# SCH_GroeiAcademie-Stimulus-Hardware-Shie.net
KiCad netlist of a schematic drawn in EasyEDA
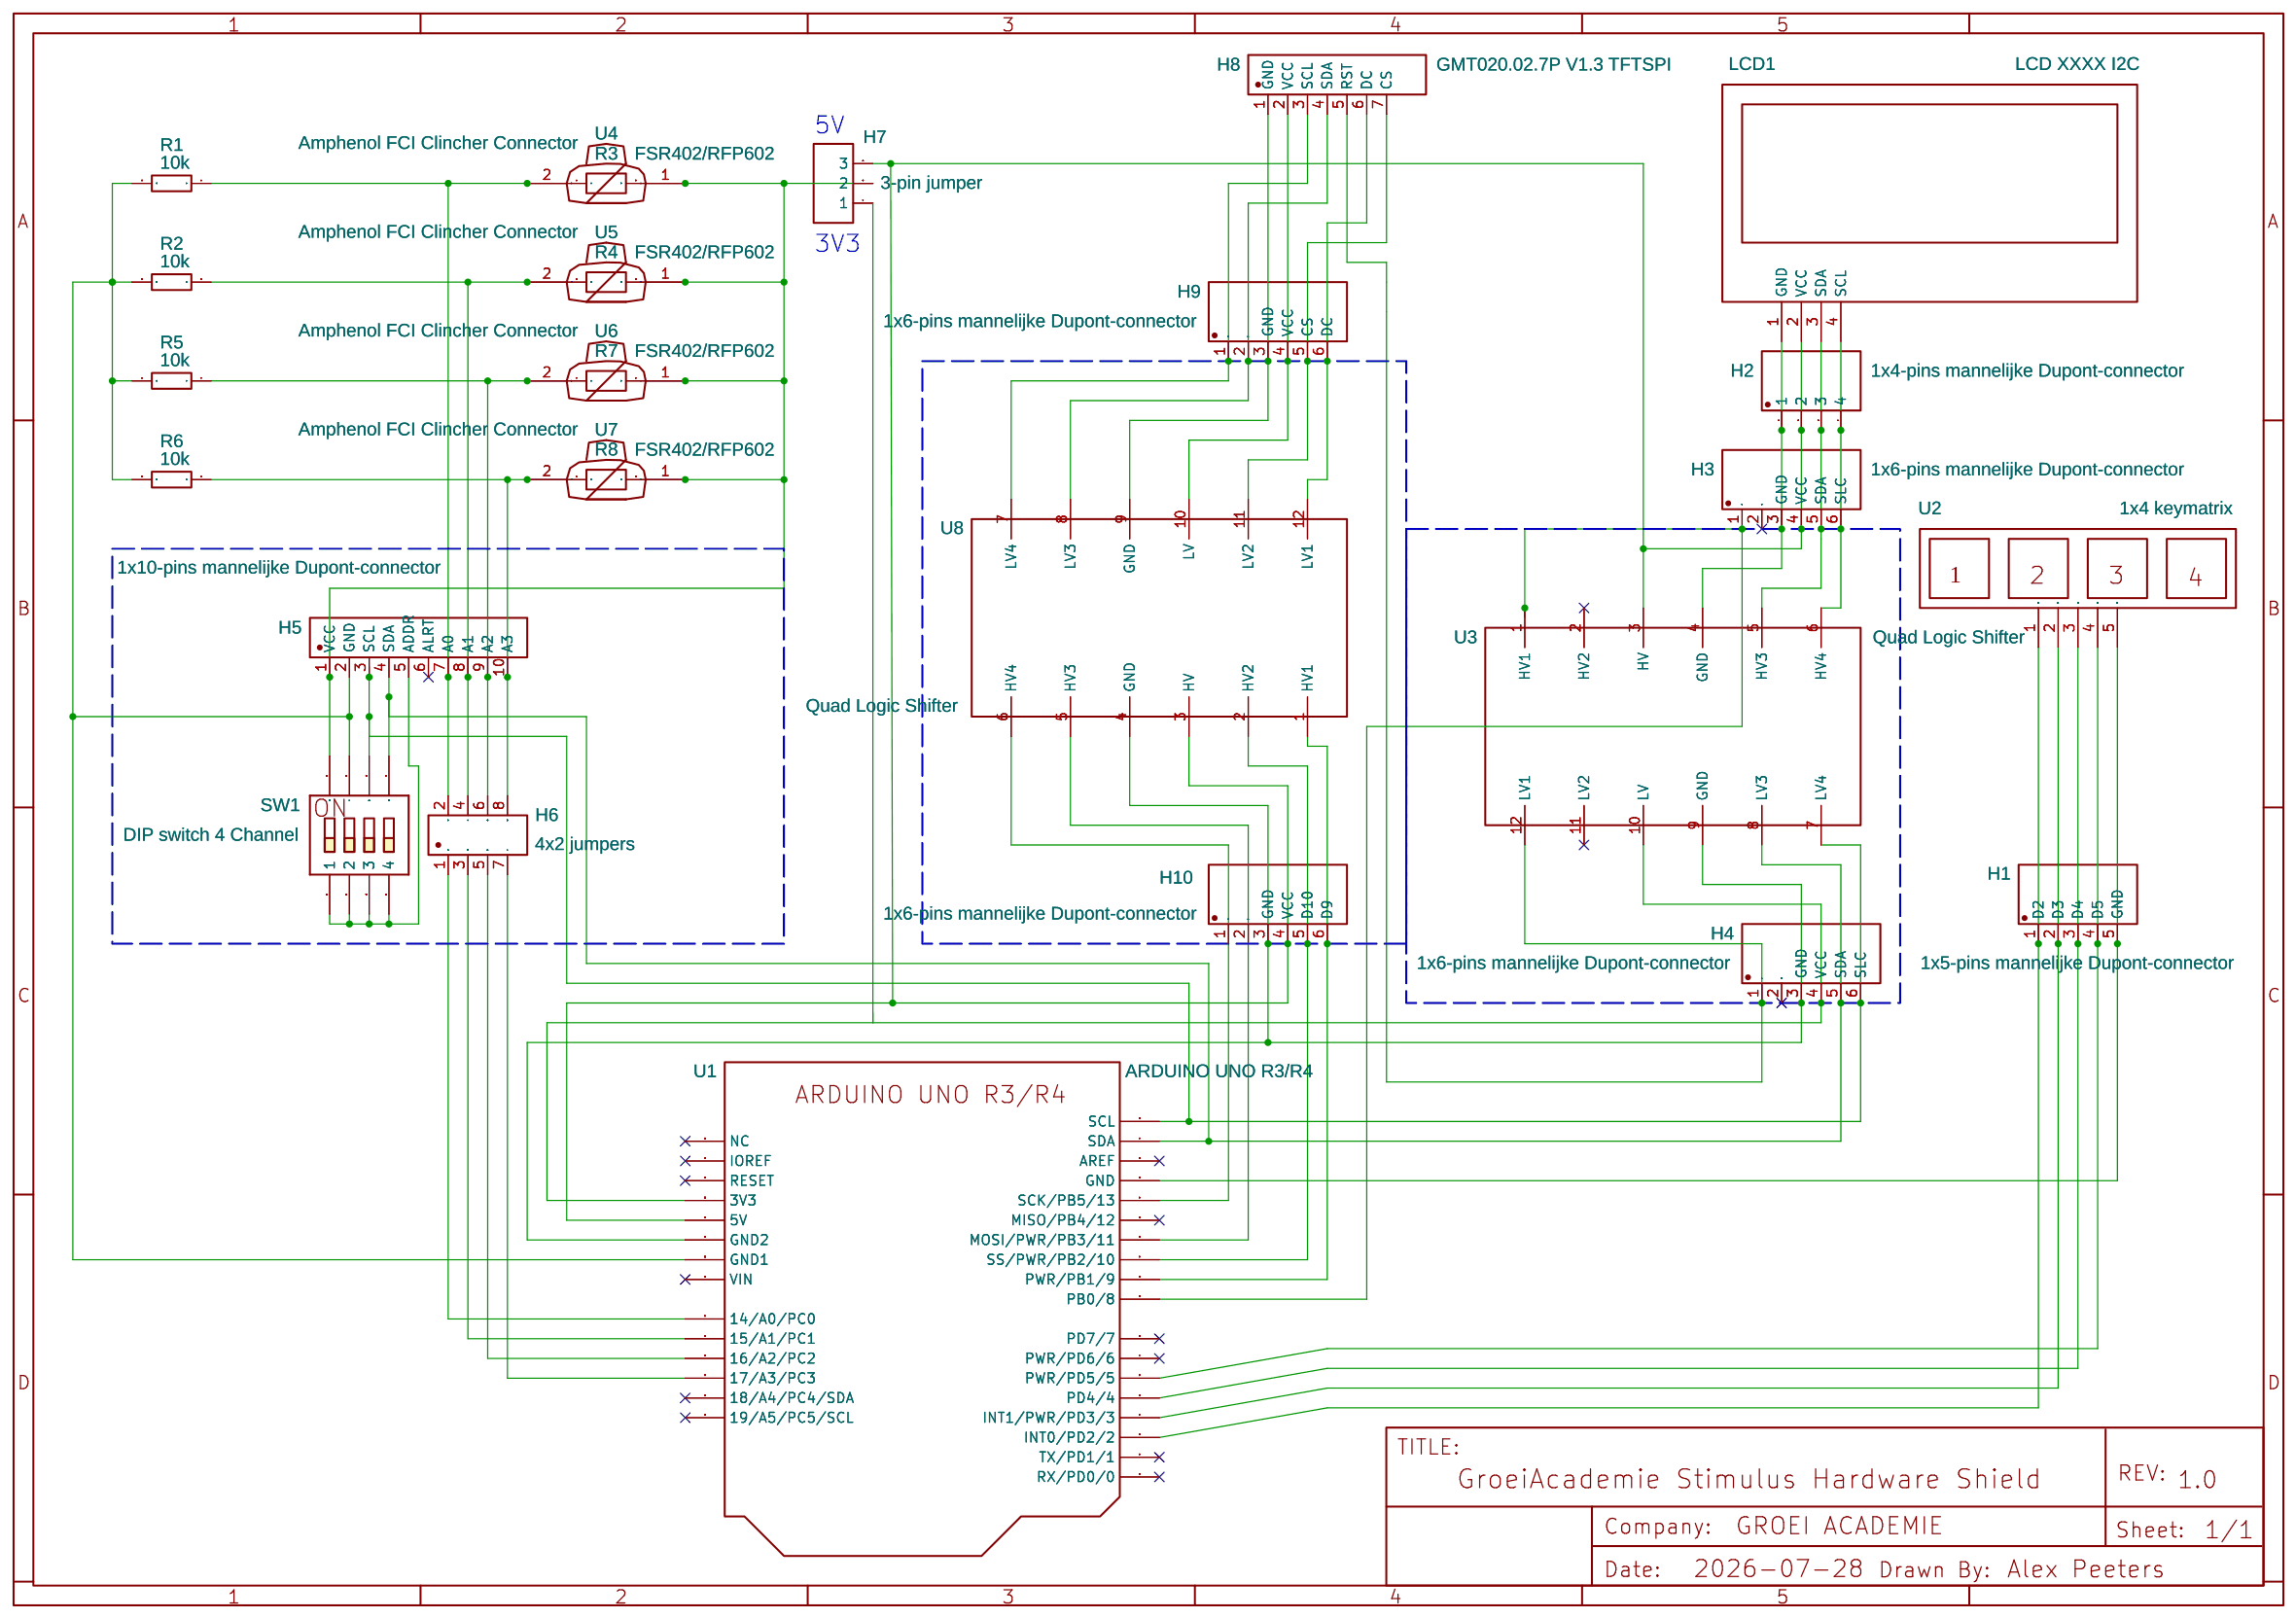
[diagram p0: schematic sheet]

(export (version "E")
  (design (tool "Eeschema 10.0.6"))
  (components
    (comp (ref "H1")
      (value "1x5-pins mannelijke Dupont-connector")
      (fields (field (name "Manufacturer Part") "B-2100S05P-A110") (field (name "Manufacturer") "Ckmtw(灿科盟)"))
      (libsource (lib "") (part "210S-1*5P L=11.6MMGold-plated black"))
    )
    (comp (ref "H2")
      (value "1x4-pins mannelijke Dupont-connector")
      (fields (field (name "Manufacturer Part") "B-2100S04P-A110") (field (name "Manufacturer") "Ckmtw(灿科盟)"))
      (libsource (lib "") (part "Header-Male-2.54_1x4"))
    )
    (comp (ref "H3")
      (value "1x6-pins mannelijke Dupont-connector")
      (fields (field (name "Manufacturer Part") "B-2100S06P-A110") (field (name "Manufacturer") "Ckmtw(灿科盟)"))
      (libsource (lib "") (part "210S-1*6P L=11.6MMGold-plated black"))
    )
    (comp (ref "H4")
      (value "1x6-pins mannelijke Dupont-connector")
      (fields (field (name "Manufacturer Part") "B-2100S06P-A110") (field (name "Manufacturer") "Ckmtw(灿科盟)"))
      (libsource (lib "") (part "210S-1*6P L=11.6MMGold-plated black"))
    )
    (comp (ref "H5")
      (value "1x10-pins mannelijke Dupont-connector")
      (fields (field (name "Manufacturer Part") "2.54-1*10") (field (name "Manufacturer") "ZHOURI(洲日)"))
      (libsource (lib "") (part "2.54-1*10"))
    )
    (comp (ref "H6")
      (value "4x2 jumpers")
      (fields (field (name "Manufacturer Part") "2.54-2*4P立贴针") (field (name "Manufacturer") "BOOMELE(博穆精密)"))
      (libsource (lib "") (part "2.54-2*4P立贴针"))
    )
    (comp (ref "H7") (value "3-pin jumper") (libsource (lib "") (part "HDR-F-2.54_1x3")))
    (comp (ref "H8")
      (value "GMT020.02.7P V1.3 TFTSPI")
      (fields (field (name "Manufacturer Part") "HDR-M-L12-3+4-1x8P-2.54"))
      (libsource (lib "") (part "PZ254R-11-08P"))
    )
    (comp (ref "H9")
      (value "1x6-pins mannelijke Dupont-connector")
      (fields (field (name "Manufacturer Part") "B-2100S06P-A110") (field (name "Manufacturer") "Ckmtw(灿科盟)"))
      (libsource (lib "") (part "210S-1*6P L=11.6MMGold-plated black_1"))
    )
    (comp (ref "H10")
      (value "1x6-pins mannelijke Dupont-connector")
      (fields (field (name "Manufacturer Part") "B-2100S06P-A110") (field (name "Manufacturer") "Ckmtw(灿科盟)"))
      (libsource (lib "") (part "210S-1*6P L=11.6MMGold-plated black_2"))
    )
    (comp (ref "LCD1") (value "LCD XXXX I2C") (libsource (lib "") (part "I2CLCD16X2_N")))
    (comp (ref "R1")
      (value "10k")
      (fields (field (name "Manufacturer") "Made in China"))
      (libsource (lib "") (part "330Ω (331) ±5%"))
    )
    (comp (ref "R2")
      (value "10k")
      (fields (field (name "Manufacturer") "Made in China"))
      (libsource (lib "") (part "330Ω (331) ±5%"))
    )
    (comp (ref "R3") (value "FSR402/RFP602") (libsource (lib "") (part "FSR402-OPCION1")))
    (comp (ref "R4") (value "FSR402/RFP602") (libsource (lib "") (part "FSR402-OPCION1")))
    (comp (ref "R5")
      (value "10k")
      (fields (field (name "Manufacturer") "Made in China"))
      (libsource (lib "") (part "330Ω (331) ±5%"))
    )
    (comp (ref "R6")
      (value "10k")
      (fields (field (name "Manufacturer") "Made in China"))
      (libsource (lib "") (part "330Ω (331) ±5%"))
    )
    (comp (ref "R7") (value "FSR402/RFP602") (libsource (lib "") (part "FSR402-OPCION1")))
    (comp (ref "R8") (value "FSR402/RFP602") (libsource (lib "") (part "FSR402-OPCION1")))
    (comp (ref "SW1")
      (value "DIP switch 4 Channel")
      (fields
        (field (name "Manufacturer Part") "DIP switch,Dip Switch,DSWB04LHGET")
        (field (name "Manufacturer") "KE")
      )
      (libsource (lib "") (part "DIP switch 4 Channel"))
    )
    (comp (ref "U1") (value "ARDUINO UNO R3/R4") (libsource (lib "") (part "ARDUINO UNO r3")))
    (comp (ref "U2") (value "1x4 keymatrix") (libsource (lib "") (part "Клавиатура 4*4")))
    (comp (ref "U3") (value "Quad Logic Shifter") (libsource (lib "") (part "Quad Logic Shifter_1")))
    (comp (ref "U4")
      (value "Amphenol FCI Clincher Connector")
      (fields (field (name "Manufacturer Part") "AT04-2P-BM02") (field (name "Manufacturer") "Amphenol"))
      (libsource (lib "") (part "AT04-2P"))
    )
    (comp (ref "U5")
      (value "Amphenol FCI Clincher Connector")
      (fields (field (name "Manufacturer Part") "AT04-2P-BM02") (field (name "Manufacturer") "Amphenol"))
      (libsource (lib "") (part "AT04-2P"))
    )
    (comp (ref "U6")
      (value "Amphenol FCI Clincher Connector")
      (fields (field (name "Manufacturer Part") "AT04-2P-BM02") (field (name "Manufacturer") "Amphenol"))
      (libsource (lib "") (part "AT04-2P"))
    )
    (comp (ref "U7")
      (value "Amphenol FCI Clincher Connector")
      (fields (field (name "Manufacturer Part") "AT04-2P-BM02") (field (name "Manufacturer") "Amphenol"))
      (libsource (lib "") (part "AT04-2P"))
    )
    (comp (ref "U8") (value "Quad Logic Shifter") (libsource (lib "") (part "Quad Logic Shifter")))
  )
  (nets
    (net (code "1") (name "Net-(H1-D2)") (class "Default")
      (node (ref "H1") (pin "1") (pinfunction "D2_1") (pintype "unspecified"))
      (node (ref "U1") (pin "3") (pinfunction "INT0/PD2/2_3") (pintype "unspecified"))
      (node (ref "U2") (pin "1") (pinfunction "C1_1") (pintype "unspecified"))
    )
    (net (code "2") (name "Net-(H1-D3)") (class "Default")
      (node (ref "H1") (pin "2") (pinfunction "D3_2") (pintype "unspecified"))
      (node (ref "U1") (pin "4") (pinfunction "INT1/PWR/PD3/3_4") (pintype "unspecified"))
      (node (ref "U2") (pin "2") (pinfunction "C2_2") (pintype "unspecified"))
    )
    (net (code "3") (name "Net-(H1-D4)") (class "Default")
      (node (ref "H1") (pin "3") (pinfunction "D4_3") (pintype "unspecified"))
      (node (ref "U1") (pin "5") (pinfunction "PD4/4_5") (pintype "unspecified"))
      (node (ref "U2") (pin "3") (pinfunction "C3_3") (pintype "unspecified"))
    )
    (net (code "4") (name "Net-(H1-D5)") (class "Default")
      (node (ref "H1") (pin "4") (pinfunction "D5_4") (pintype "unspecified"))
      (node (ref "U1") (pin "6") (pinfunction "PWR/PD5/5_6") (pintype "unspecified"))
      (node (ref "U2") (pin "4") (pinfunction "R1_4") (pintype "unspecified"))
    )
    (net (code "5") (name "Net-(H1-GND)") (class "Default")
      (node (ref "H1") (pin "5") (pinfunction "GND_5") (pintype "unspecified"))
      (node (ref "U1") (pin "15") (pinfunction "GND_15") (pintype "passive"))
      (node (ref "U2") (pin "5") (pinfunction "R2_5") (pintype "unspecified"))
    )
    (net (code "6") (name "Net-(H3-GND)") (class "Default")
      (node (ref "H2") (pin "1") (pinfunction "1_1") (pintype "unspecified"))
      (node (ref "H3") (pin "3") (pinfunction "GND_3") (pintype "unspecified"))
      (node (ref "LCD1") (pin "1") (pinfunction "GND_1") (pintype "unspecified"))
      (node (ref "U3") (pin "4") (pinfunction "GND_4") (pintype "unspecified"))
    )
    (net (code "7") (name "Net-(H3-SDA)") (class "Default")
      (node (ref "H2") (pin "3") (pinfunction "3_3") (pintype "unspecified"))
      (node (ref "H3") (pin "5") (pinfunction "SDA_5") (pintype "unspecified"))
      (node (ref "LCD1") (pin "3") (pinfunction "SDA_3") (pintype "unspecified"))
      (node (ref "U3") (pin "5") (pinfunction "HV3_5") (pintype "unspecified"))
    )
    (net (code "8") (name "Net-(H3-SLC)") (class "Default")
      (node (ref "H2") (pin "4") (pinfunction "4_4") (pintype "unspecified"))
      (node (ref "H3") (pin "6") (pinfunction "SLC_6") (pintype "unspecified"))
      (node (ref "LCD1") (pin "4") (pinfunction "SCL_4") (pintype "unspecified"))
      (node (ref "U3") (pin "6") (pinfunction "HV4_6") (pintype "unspecified"))
    )
    (net (code "9") (name "Net-(H4-SDA)") (class "Default")
      (node (ref "H4") (pin "5") (pinfunction "SDA_5") (pintype "unspecified"))
      (node (ref "H5") (pin "4") (pinfunction "SDA_4") (pintype "unspecified"))
      (node (ref "SW1") (pin "4I") (pinfunction "5_4I") (pintype "input"))
      (node (ref "U1") (pin "17") (pinfunction "SDA_17") (pintype "unspecified"))
      (node (ref "U3") (pin "8") (pinfunction "LV3_8") (pintype "unspecified"))
    )
    (net (code "10") (name "Net-(H4-SLC)") (class "Default")
      (node (ref "H4") (pin "6") (pinfunction "SLC_6") (pintype "unspecified"))
      (node (ref "H5") (pin "3") (pinfunction "SCL_3") (pintype "unspecified"))
      (node (ref "SW1") (pin "3I") (pinfunction "6_3I") (pintype "input"))
      (node (ref "U1") (pin "18") (pinfunction "SCL_18") (pintype "unspecified"))
      (node (ref "U3") (pin "7") (pinfunction "LV4_7") (pintype "unspecified"))
    )
    (net (code "11") (name "Net-(H4-VCC)") (class "Default")
      (node (ref "H4") (pin "4") (pinfunction "VCC_4") (pintype "unspecified"))
      (node (ref "U1") (pin "29") (pinfunction "3V3_29") (pintype "passive"))
      (node (ref "U3") (pin "10") (pinfunction "LV_10") (pintype "unspecified"))
    )
    (net (code "12") (name "Net-(H5-A0)") (class "Default")
      (node (ref "H5") (pin "7") (pinfunction "A0_7") (pintype "unspecified"))
      (node (ref "H6") (pin "2") (pinfunction "2_2") (pintype "unspecified"))
      (node (ref "R1") (pin "1") (pinfunction "1_1") (pintype "unspecified"))
      (node (ref "R3") (pin "1") (pinfunction "1_1") (pintype "unspecified"))
      (node (ref "U4") (pin "2") (pinfunction "2_2") (pintype "unspecified"))
    )
    (net (code "13") (name "Net-(H5-A1)") (class "Default")
      (node (ref "H5") (pin "8") (pinfunction "A1_8") (pintype "unspecified"))
      (node (ref "H6") (pin "4") (pinfunction "4_4") (pintype "unspecified"))
      (node (ref "R2") (pin "1") (pinfunction "1_1") (pintype "unspecified"))
      (node (ref "R4") (pin "1") (pinfunction "1_1") (pintype "unspecified"))
      (node (ref "U5") (pin "2") (pinfunction "2_2") (pintype "unspecified"))
    )
    (net (code "14") (name "Net-(H5-A2)") (class "Default")
      (node (ref "H5") (pin "9") (pinfunction "A2_9") (pintype "unspecified"))
      (node (ref "H6") (pin "6") (pinfunction "6_6") (pintype "unspecified"))
      (node (ref "R5") (pin "1") (pinfunction "1_1") (pintype "unspecified"))
      (node (ref "R7") (pin "1") (pinfunction "1_1") (pintype "unspecified"))
      (node (ref "U6") (pin "2") (pinfunction "2_2") (pintype "unspecified"))
    )
    (net (code "15") (name "Net-(H5-A3)") (class "Default")
      (node (ref "H5") (pin "10") (pinfunction "A3_10") (pintype "unspecified"))
      (node (ref "H6") (pin "8") (pinfunction "8_8") (pintype "unspecified"))
      (node (ref "R6") (pin "1") (pinfunction "1_1") (pintype "unspecified"))
      (node (ref "R8") (pin "1") (pinfunction "1_1") (pintype "unspecified"))
      (node (ref "U7") (pin "2") (pinfunction "2_2") (pintype "unspecified"))
    )
    (net (code "16") (name "Net-(H5-ADDR)") (class "Default")
      (node (ref "H5") (pin "5") (pinfunction "ADDR_5") (pintype "unspecified"))
      (node (ref "SW1") (pin "1O") (pinfunction "1_1O") (pintype "input"))
      (node (ref "SW1") (pin "2O") (pinfunction "2_2O") (pintype "input"))
      (node (ref "SW1") (pin "3O") (pinfunction "3_3O") (pintype "input"))
      (node (ref "SW1") (pin "4O") (pinfunction "4_4O") (pintype "input"))
    )
    (net (code "17") (name "Net-(H5-GND)") (class "Default")
      (node (ref "H5") (pin "2") (pinfunction "GND_2") (pintype "unspecified"))
      (node (ref "R1") (pin "2") (pinfunction "2_2") (pintype "unspecified"))
      (node (ref "R2") (pin "2") (pinfunction "2_2") (pintype "unspecified"))
      (node (ref "R5") (pin "2") (pinfunction "2_2") (pintype "unspecified"))
      (node (ref "R6") (pin "2") (pinfunction "2_2") (pintype "unspecified"))
      (node (ref "SW1") (pin "2I") (pinfunction "7_2I") (pintype "input"))
      (node (ref "U1") (pin "26") (pinfunction "GND1_26") (pintype "passive"))
    )
    (net (code "18") (name "Net-(H5-VCC)") (class "Default")
      (node (ref "H5") (pin "1") (pinfunction "VCC_1") (pintype "unspecified"))
      (node (ref "H7") (pin "2") (pinfunction "2_2") (pintype "input"))
      (node (ref "R3") (pin "2") (pinfunction "2_2") (pintype "unspecified"))
      (node (ref "R4") (pin "2") (pinfunction "2_2") (pintype "unspecified"))
      (node (ref "R7") (pin "2") (pinfunction "2_2") (pintype "unspecified"))
      (node (ref "R8") (pin "2") (pinfunction "2_2") (pintype "unspecified"))
      (node (ref "SW1") (pin "1I") (pinfunction "8_1I") (pintype "input"))
      (node (ref "U4") (pin "1") (pinfunction "1_1") (pintype "unspecified"))
      (node (ref "U5") (pin "1") (pinfunction "1_1") (pintype "unspecified"))
      (node (ref "U6") (pin "1") (pinfunction "1_1") (pintype "unspecified"))
      (node (ref "U7") (pin "1") (pinfunction "1_1") (pintype "unspecified"))
    )
    (net (code "19") (name "Net-(H8-CS)") (class "Default")
      (node (ref "H8") (pin "7") (pinfunction "CS_7") (pintype "unspecified"))
      (node (ref "H9") (pin "5") (pinfunction "CS_5") (pintype "unspecified"))
      (node (ref "U8") (pin "11") (pinfunction "LV2_11") (pintype "unspecified"))
    )
    (net (code "20") (name "Net-(H8-DC)") (class "Default")
      (node (ref "H8") (pin "6") (pinfunction "DC_6") (pintype "unspecified"))
      (node (ref "H9") (pin "6") (pinfunction "DC_6") (pintype "unspecified"))
      (node (ref "U8") (pin "12") (pinfunction "LV1_12") (pintype "unspecified"))
    )
    (net (code "21") (name "Net-(H8-GND)") (class "Default")
      (node (ref "H8") (pin "1") (pinfunction "GND_1") (pintype "unspecified"))
      (node (ref "H9") (pin "3") (pinfunction "GND_3") (pintype "unspecified"))
      (node (ref "U8") (pin "9") (pinfunction "GND_9") (pintype "unspecified"))
    )
    (net (code "22") (name "Net-(H8-RST)") (class "Default")
      (node (ref "H4") (pin "1") (pinfunction "1_1") (pintype "unspecified"))
      (node (ref "H8") (pin "5") (pinfunction "RST_5") (pintype "unspecified"))
      (node (ref "U3") (pin "12") (pinfunction "LV1_12") (pintype "unspecified"))
    )
    (net (code "23") (name "Net-(H8-SCL)") (class "Default")
      (node (ref "H8") (pin "3") (pinfunction "SCL_3") (pintype "unspecified"))
      (node (ref "H9") (pin "1") (pinfunction "1_1") (pintype "unspecified"))
      (node (ref "U8") (pin "7") (pinfunction "LV4_7") (pintype "unspecified"))
    )
    (net (code "24") (name "Net-(H8-SDA)") (class "Default")
      (node (ref "H8") (pin "4") (pinfunction "SDA_4") (pintype "unspecified"))
      (node (ref "H9") (pin "2") (pinfunction "2_2") (pintype "unspecified"))
      (node (ref "U8") (pin "8") (pinfunction "LV3_8") (pintype "unspecified"))
    )
    (net (code "25") (name "Net-(H8-VCC)") (class "Default")
      (node (ref "H8") (pin "2") (pinfunction "VCC_2") (pintype "unspecified"))
      (node (ref "H9") (pin "4") (pinfunction "VCC_4") (pintype "unspecified"))
      (node (ref "U8") (pin "10") (pinfunction "LV_10") (pintype "unspecified"))
    )
    (net (code "26") (name "Net-(H10-D9)") (class "Default")
      (node (ref "H10") (pin "6") (pinfunction "D9_6") (pintype "unspecified"))
      (node (ref "U1") (pin "10") (pinfunction "PWR/PB1/9_10") (pintype "unspecified"))
      (node (ref "U8") (pin "1") (pinfunction "HV1_1") (pintype "unspecified"))
    )
    (net (code "27") (name "Net-(H10-D10)") (class "Default")
      (node (ref "H10") (pin "5") (pinfunction "D10_5") (pintype "unspecified"))
      (node (ref "U1") (pin "11") (pinfunction "SS/PWR/PB2/10_11") (pintype "unspecified"))
      (node (ref "U8") (pin "2") (pinfunction "HV2_2") (pintype "unspecified"))
    )
    (net (code "28") (name "Net-(H10-GND)") (class "Default")
      (node (ref "H10") (pin "3") (pinfunction "GND_3") (pintype "unspecified"))
      (node (ref "H4") (pin "3") (pinfunction "GND_3") (pintype "unspecified"))
      (node (ref "U1") (pin "27") (pinfunction "GND2_27") (pintype "passive"))
      (node (ref "U3") (pin "9") (pinfunction "GND_9") (pintype "unspecified"))
      (node (ref "U8") (pin "4") (pinfunction "GND_4") (pintype "unspecified"))
    )
    (net (code "29") (name "Net-(H10-VCC)") (class "Default")
      (node (ref "H10") (pin "4") (pinfunction "VCC_4") (pintype "unspecified"))
      (node (ref "H2") (pin "2") (pinfunction "2_2") (pintype "unspecified"))
      (node (ref "H3") (pin "4") (pinfunction "VCC_4") (pintype "unspecified"))
      (node (ref "H7") (pin "3") (pinfunction "3_3") (pintype "input"))
      (node (ref "LCD1") (pin "2") (pinfunction "VCC_2") (pintype "unspecified"))
      (node (ref "U1") (pin "28") (pinfunction "5V_28") (pintype "passive"))
      (node (ref "U3") (pin "3") (pinfunction "HV_3") (pintype "unspecified"))
      (node (ref "U8") (pin "3") (pinfunction "HV_3") (pintype "unspecified"))
    )
    (net (code "30") (name "Net-(U1-14{slash}A0{slash}PC0)") (class "Default")
      (node (ref "H6") (pin "1") (pinfunction "1_1") (pintype "unspecified"))
      (node (ref "U1") (pin "24") (pinfunction "14/A0/PC0_24") (pintype "unspecified"))
    )
    (net (code "31") (name "Net-(U1-15{slash}A1{slash}PC1)") (class "Default")
      (node (ref "H6") (pin "3") (pinfunction "3_3") (pintype "unspecified"))
      (node (ref "U1") (pin "23") (pinfunction "15/A1/PC1_23") (pintype "unspecified"))
    )
    (net (code "32") (name "Net-(U1-16{slash}A2{slash}PC2)") (class "Default")
      (node (ref "H6") (pin "5") (pinfunction "5_5") (pintype "unspecified"))
      (node (ref "U1") (pin "22") (pinfunction "16/A2/PC2_22") (pintype "unspecified"))
    )
    (net (code "33") (name "Net-(U1-17{slash}A3{slash}PC3)") (class "Default")
      (node (ref "H6") (pin "7") (pinfunction "7_7") (pintype "unspecified"))
      (node (ref "U1") (pin "21") (pinfunction "17/A3/PC3_21") (pintype "unspecified"))
    )
    (net (code "34") (name "Net-(U1-MOSI{slash}PWR{slash}PB3{slash}11)") (class "Default")
      (node (ref "H10") (pin "2") (pinfunction "2_2") (pintype "unspecified"))
      (node (ref "U1") (pin "12") (pinfunction "MOSI/PWR/PB3/11_12") (pintype "unspecified"))
    )
    (net (code "35") (name "Net-(U1-PB0{slash}8)") (class "Default")
      (node (ref "H3") (pin "1") (pinfunction "1_1") (pintype "unspecified"))
      (node (ref "U1") (pin "9") (pinfunction "PB0/8_9") (pintype "unspecified"))
      (node (ref "U3") (pin "1") (pinfunction "HV1_1") (pintype "unspecified"))
    )
    (net (code "36") (name "Net-(U1-SCK{slash}PB5{slash}13)") (class "Default")
      (node (ref "H10") (pin "1") (pinfunction "1_1") (pintype "unspecified"))
      (node (ref "U1") (pin "14") (pinfunction "SCK/PB5/13_14") (pintype "unspecified"))
    )
    (net (code "37") (name "unconnected-(H3-Pad2)") (class "Default")
      (node (ref "H3") (pin "2") (pinfunction "2_2") (pintype "unspecified+no_connect"))
    )
    (net (code "38") (name "unconnected-(H4-Pad2)") (class "Default")
      (node (ref "H4") (pin "2") (pinfunction "2_2") (pintype "unspecified+no_connect"))
    )
    (net (code "39") (name "unconnected-(H5-ALRT-Pad6)") (class "Default")
      (node (ref "H5") (pin "6") (pinfunction "ALRT_6") (pintype "unspecified+no_connect"))
    )
    (net (code "40") (name "unconnected-(H7-Pad1)") (class "Default")
      (node (ref "H7") (pin "1") (pinfunction "1_1") (pintype "input"))
    )
    (net (code "41") (name "unconnected-(U1-18{slash}A4{slash}PC4{slash}SDA-Pad20)") (class "Default")
      (node (ref "U1") (pin "20") (pinfunction "18/A4/PC4/SDA_20") (pintype "unspecified+no_connect"))
    )
    (net (code "42") (name "unconnected-(U1-19{slash}A5{slash}PC5{slash}SCL-Pad19)") (class "Default")
      (node (ref "U1") (pin "19") (pinfunction "19/A5/PC5/SCL_19") (pintype "unspecified+no_connect"))
    )
    (net (code "43") (name "unconnected-(U1-AREF-Pad16)") (class "Default")
      (node (ref "U1") (pin "16") (pinfunction "AREF_16") (pintype "unspecified+no_connect"))
    )
    (net (code "44") (name "unconnected-(U1-IOREF-Pad31)") (class "Default")
      (node (ref "U1") (pin "31") (pinfunction "IOREF_31") (pintype "unspecified+no_connect"))
    )
    (net (code "45") (name "unconnected-(U1-MISO{slash}PB4{slash}12-Pad13)") (class "Default")
      (node (ref "U1") (pin "13") (pinfunction "MISO/PB4/12_13") (pintype "unspecified+no_connect"))
    )
    (net (code "46") (name "unconnected-(U1-NC-Pad32)") (class "Default")
      (node (ref "U1") (pin "32") (pinfunction "NC_32") (pintype "unspecified+no_connect"))
    )
    (net (code "47") (name "unconnected-(U1-PD7{slash}7-Pad8)") (class "Default")
      (node (ref "U1") (pin "8") (pinfunction "PD7/7_8") (pintype "unspecified+no_connect"))
    )
    (net (code "48") (name "unconnected-(U1-PWR{slash}PD6{slash}6-Pad7)") (class "Default")
      (node (ref "U1") (pin "7") (pinfunction "PWR/PD6/6_7") (pintype "unspecified+no_connect"))
    )
    (net (code "49") (name "unconnected-(U1-RESET-Pad30)") (class "Default")
      (node (ref "U1") (pin "30") (pinfunction "RESET_30") (pintype "unspecified+no_connect"))
    )
    (net (code "50") (name "unconnected-(U1-RX{slash}PD0{slash}0-Pad1)") (class "Default")
      (node (ref "U1") (pin "1") (pinfunction "RX/PD0/0_1") (pintype "unspecified+no_connect"))
    )
    (net (code "51") (name "unconnected-(U1-TX{slash}PD1{slash}1-Pad2)") (class "Default")
      (node (ref "U1") (pin "2") (pinfunction "TX/PD1/1_2") (pintype "unspecified+no_connect"))
    )
    (net (code "52") (name "unconnected-(U1-VIN-Pad25)") (class "Default")
      (node (ref "U1") (pin "25") (pinfunction "VIN_25") (pintype "passive+no_connect"))
    )
    (net (code "53") (name "unconnected-(U3-HV2-Pad2)") (class "Default")
      (node (ref "U3") (pin "2") (pinfunction "HV2_2") (pintype "unspecified+no_connect"))
    )
    (net (code "54") (name "unconnected-(U3-LV2-Pad11)") (class "Default")
      (node (ref "U3") (pin "11") (pinfunction "LV2_11") (pintype "unspecified+no_connect"))
    )
    (net (code "55") (name "unconnected-(U8-HV3-Pad5)") (class "Default")
      (node (ref "U8") (pin "5") (pinfunction "HV3_5") (pintype "unspecified"))
    )
    (net (code "56") (name "unconnected-(U8-HV4-Pad6)") (class "Default")
      (node (ref "U8") (pin "6") (pinfunction "HV4_6") (pintype "unspecified"))
    )
  )
)
